# Snowman.net
KiCad netlist of a schematic drawn in EAGLE
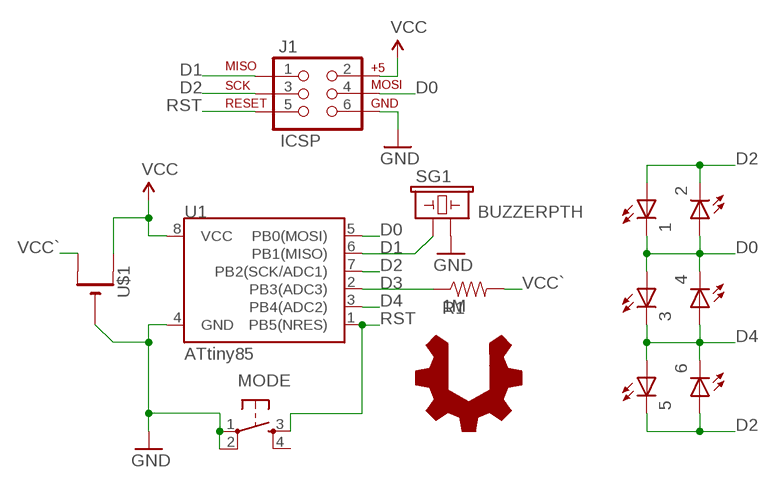
[diagram p0: schematic, sheet 1]

(export (version "E")
  (design (tool "Eeschema 10.0.6"))
  (components
    (comp (ref "1")
      (value "LEDOVAL")
      (footprint "eagle-import:LED-OVAL")
      (libsource (lib "eagle-import") (part "LEDOVAL"))
    )
    (comp (ref "2")
      (value "LEDOVAL")
      (footprint "eagle-import:LED-OVAL")
      (libsource (lib "eagle-import") (part "LEDOVAL"))
    )
    (comp (ref "3")
      (value "LEDOVAL")
      (footprint "eagle-import:LED-OVAL")
      (libsource (lib "eagle-import") (part "LEDOVAL"))
    )
    (comp (ref "4")
      (value "LEDOVAL")
      (footprint "eagle-import:LED-OVAL")
      (libsource (lib "eagle-import") (part "LEDOVAL"))
    )
    (comp (ref "5")
      (value "LEDOVAL")
      (footprint "eagle-import:LED-OVAL")
      (libsource (lib "eagle-import") (part "LEDOVAL"))
    )
    (comp (ref "6")
      (value "LEDOVAL")
      (footprint "eagle-import:LED-OVAL")
      (libsource (lib "eagle-import") (part "LEDOVAL"))
    )
    (comp (ref "J1")
      (value "ICSP")
      (footprint "eagle-import:2X3-NS")
      (libsource (lib "eagle-import") (part "AVR_SPI_PRG_6LABELED"))
    )
    (comp (ref "MODE")
      (value "TAC_SWITCHPTH")
      (footprint "eagle-import:TACTILE-PTH")
      (libsource (lib "eagle-import") (part "TAC_SWITCHPTH"))
    )
    (comp (ref "R1")
      (value "1M")
      (footprint "eagle-import:AXIAL-0.3")
      (libsource (lib "eagle-import") (part "RESISTORAXIAL-0.3"))
    )
    (comp (ref "SG1")
      (value "BUZZERPTH")
      (footprint "eagle-import:BUZZER-12MM")
      (libsource (lib "eagle-import") (part "BUZZERPTH"))
    )
    (comp (ref "U$1")
      (value "CR2032THM")
      (footprint "eagle-import:CR2032-THRU")
      (libsource (lib "eagle-import") (part "CR2032THM"))
    )
    (comp (ref "U$2")
      (value "USER_HACKABLE")
      (footprint "eagle-import:USER_HACKABLE")
      (libsource (lib "eagle-import") (part "USER_HACKABLE"))
    )
    (comp (ref "U1")
      (value "ATtiny85")
      (footprint "eagle-import:DIP08")
      (libsource (lib "eagle-import") (part "ATTINY45TINY85-20-DIP"))
    )
  )
  (nets
    (net (code "1") (name "/D0") (class "Default")
      (node (ref "1") (pin "CATHODE") (pinfunction "C_CATHODE") (pintype "passive"))
      (node (ref "2") (pin "ANODE") (pinfunction "A_ANODE") (pintype "passive"))
      (node (ref "3") (pin "ANODE") (pinfunction "A_ANODE") (pintype "passive"))
      (node (ref "4") (pin "CATHODE") (pinfunction "C_CATHODE") (pintype "passive"))
      (node (ref "J1") (pin "4") (pinfunction "MOSI_4") (pintype "passive"))
      (node (ref "U1") (pin "5") (pinfunction "PB0(MOSI)_5") (pintype "bidirectional"))
    )
    (net (code "2") (name "/D1") (class "Default")
      (node (ref "J1") (pin "1") (pinfunction "MISO_1") (pintype "passive"))
      (node (ref "SG1") (pin "+") (pinfunction "1_+") (pintype "passive"))
      (node (ref "U1") (pin "6") (pinfunction "PB1(MISO)_6") (pintype "bidirectional"))
    )
    (net (code "3") (name "/D2") (class "Default")
      (node (ref "1") (pin "ANODE") (pinfunction "A_ANODE") (pintype "passive"))
      (node (ref "2") (pin "CATHODE") (pinfunction "C_CATHODE") (pintype "passive"))
      (node (ref "5") (pin "CATHODE") (pinfunction "C_CATHODE") (pintype "passive"))
      (node (ref "6") (pin "ANODE") (pinfunction "A_ANODE") (pintype "passive"))
      (node (ref "J1") (pin "3") (pinfunction "SCK_3") (pintype "passive"))
      (node (ref "U1") (pin "7") (pinfunction "PB2(SCK/ADC1)_7") (pintype "bidirectional"))
    )
    (net (code "4") (name "/D3") (class "Default")
      (node (ref "R1") (pin "P$1") (pinfunction "1_P$1") (pintype "passive"))
      (node (ref "U1") (pin "2") (pinfunction "PB3(ADC3)_2") (pintype "bidirectional"))
    )
    (net (code "5") (name "/D4") (class "Default")
      (node (ref "3") (pin "CATHODE") (pinfunction "C_CATHODE") (pintype "passive"))
      (node (ref "4") (pin "ANODE") (pinfunction "A_ANODE") (pintype "passive"))
      (node (ref "5") (pin "ANODE") (pinfunction "A_ANODE") (pintype "passive"))
      (node (ref "6") (pin "CATHODE") (pinfunction "C_CATHODE") (pintype "passive"))
      (node (ref "U1") (pin "3") (pinfunction "PB4(ADC2)_3") (pintype "bidirectional"))
    )
    (net (code "6") (name "/RST") (class "Default")
      (node (ref "J1") (pin "5") (pinfunction "RST_5") (pintype "passive"))
      (node (ref "MODE") (pin "3") (pinfunction "3_3") (pintype "passive"))
      (node (ref "U1") (pin "1") (pinfunction "PB5(NRES)_1") (pintype "bidirectional"))
    )
    (net (code "7") (name "/VCC`") (class "Default")
      (node (ref "R1") (pin "P$2") (pinfunction "2_P$2") (pintype "passive"))
      (node (ref "U$1") (pin "+2") (pinfunction "+1_+2") (pintype "passive"))
    )
    (net (code "8") (name "GND") (class "Default")
      (node (ref "J1") (pin "6") (pinfunction "GND_6") (pintype "passive"))
      (node (ref "MODE") (pin "1") (pinfunction "1_1") (pintype "passive"))
      (node (ref "MODE") (pin "2") (pinfunction "2_2") (pintype "passive"))
      (node (ref "SG1") (pin "-") (pinfunction "2_-") (pintype "passive"))
      (node (ref "U$1") (pin "-") (pinfunction "-_-") (pintype "passive"))
      (node (ref "U1") (pin "4") (pinfunction "GND_4") (pintype "bidirectional"))
    )
    (net (code "9") (name "VCC") (class "Default")
      (node (ref "J1") (pin "2") (pinfunction "V+_2") (pintype "passive"))
      (node (ref "U$1") (pin "+1") (pinfunction "+_+1") (pintype "passive"))
      (node (ref "U1") (pin "8") (pinfunction "VCC_8") (pintype "bidirectional"))
    )
    (net (code "10") (name "unconnected-(MODE-Pad4)") (class "Default")
      (node (ref "MODE") (pin "4") (pinfunction "4_4") (pintype "passive"))
    )
  )
)
